# Lab_Controller_Board_v04.net
KiCad netlist of a schematic drawn in EAGLE
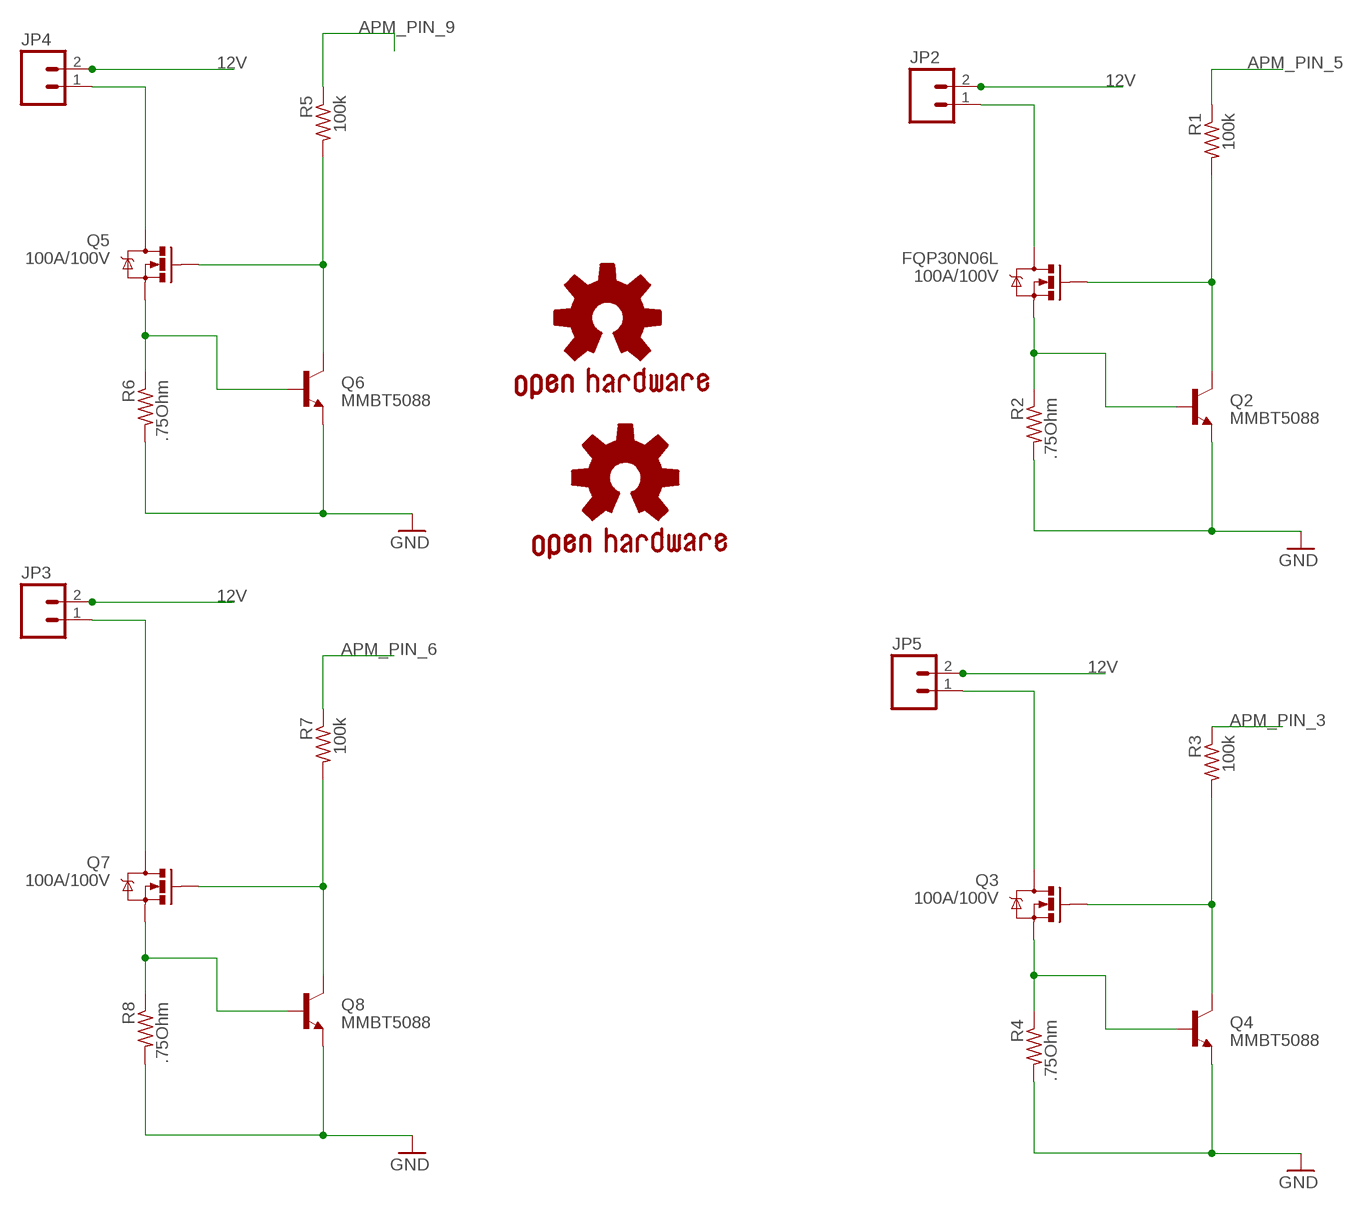
[diagram p0: schematic, sheet 1]
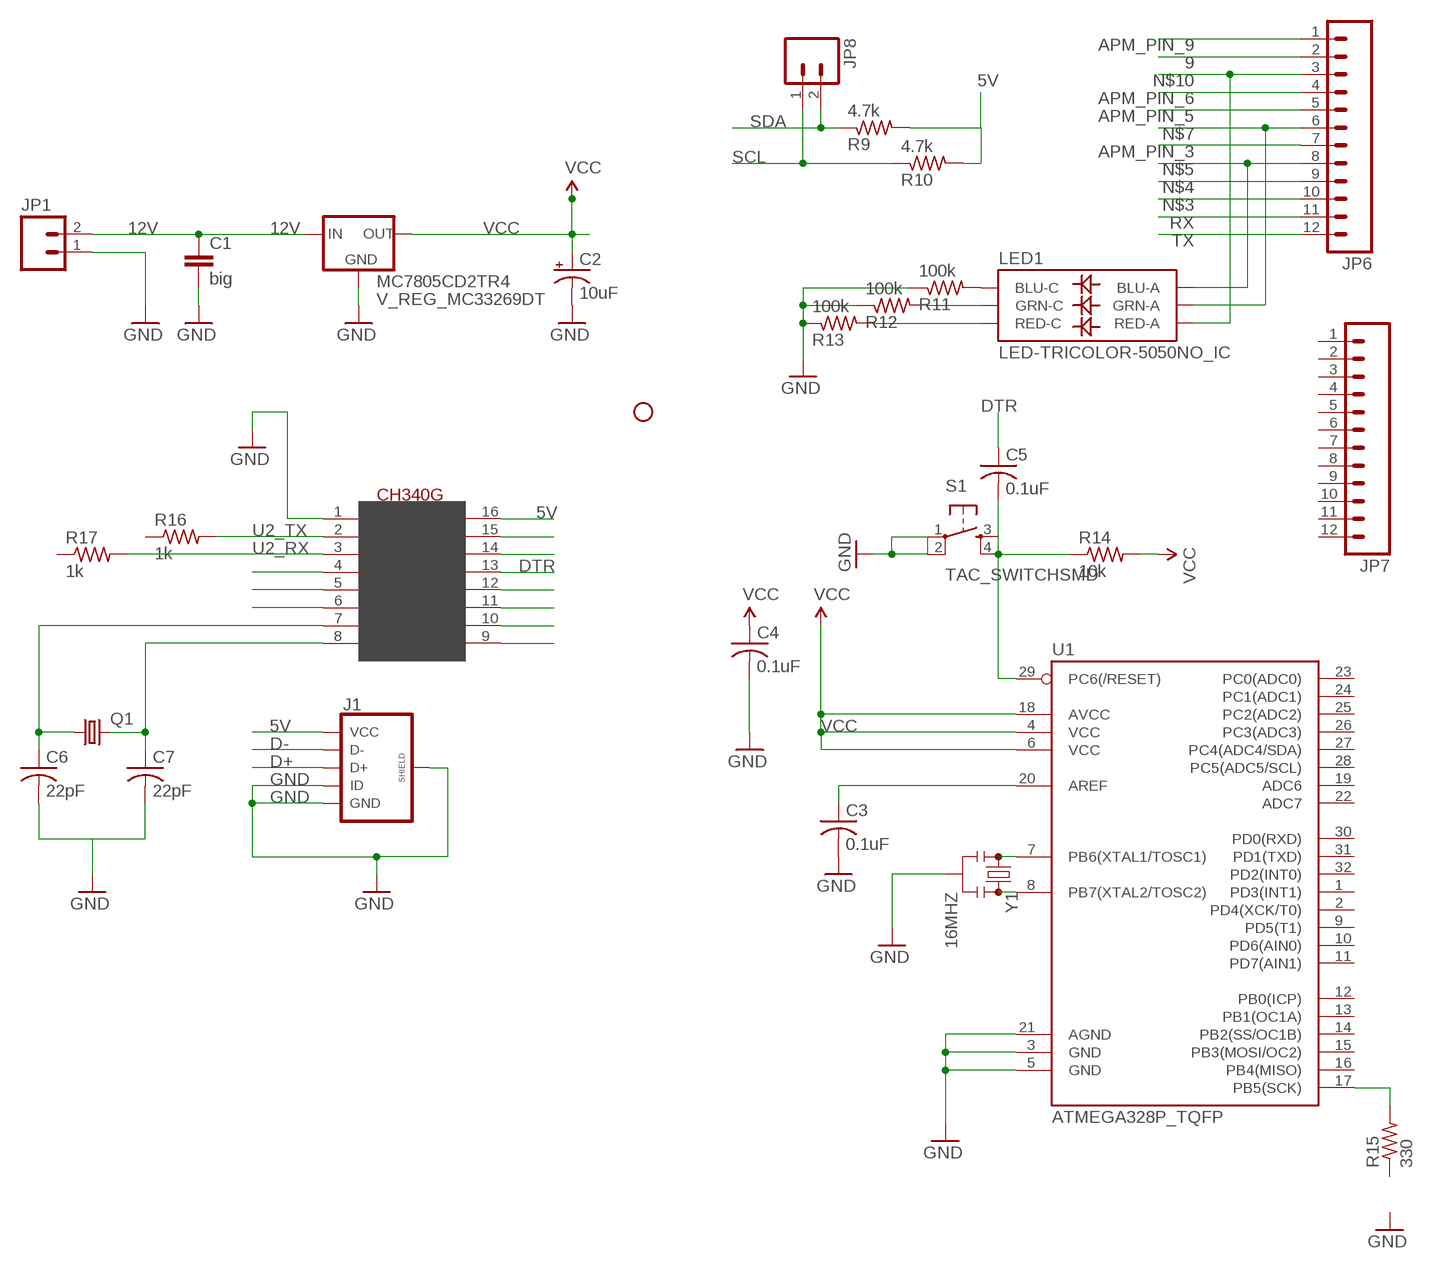
[diagram p1: schematic, sheet 2]

(export (version "E")
  (design (tool "Eeschema 10.0.6"))
  (components
    (comp (ref "FQP30N06L")
      (value "100A/100V")
      (footprint "eagle-import:TO-263_D2PAK")
      (libsource (lib "eagle-import") (part "MOSFET-NCHANNELPSMN7R0"))
    )
    (comp (ref "GOLD_ORB_SM1")
      (value "OSHWLOGO_GOLD_ORB_MED")
      (footprint "eagle-import:OSHW1")
      (libsource (lib "eagle-import") (part "OSHWLOGO_GOLD_ORB_MED"))
    )
    (comp (ref "GOLD_ORB_SM2")
      (value "OSHWLOGO_GOLD_ORB_SM")
      (footprint "eagle-import:OSHW2")
      (libsource (lib "eagle-import") (part "OSHWLOGO_GOLD_ORB_SM"))
    )
    (comp (ref "JP2")
      (value "M025MM")
      (footprint "eagle-import:SCREWTERMINAL-5MM-2")
      (libsource (lib "eagle-import") (part "M025MM"))
    )
    (comp (ref "JP3")
      (value "M025MM")
      (footprint "eagle-import:SCREWTERMINAL-5MM-2")
      (libsource (lib "eagle-import") (part "M025MM"))
    )
    (comp (ref "JP4")
      (value "M025MM")
      (footprint "eagle-import:SCREWTERMINAL-5MM-2")
      (libsource (lib "eagle-import") (part "M025MM"))
    )
    (comp (ref "JP5")
      (value "M025MM")
      (footprint "eagle-import:SCREWTERMINAL-5MM-2")
      (libsource (lib "eagle-import") (part "M025MM"))
    )
    (comp (ref "Q2")
      (value "MMBT5088")
      (footprint "eagle-import:SOT23-3")
      (libsource (lib "eagle-import") (part "TRANSISTOR_NPNMMBT5088"))
    )
    (comp (ref "Q3")
      (value "100A/100V")
      (footprint "eagle-import:TO-263_D2PAK")
      (libsource (lib "eagle-import") (part "MOSFET-NCHANNELPSMN7R0"))
    )
    (comp (ref "Q4")
      (value "MMBT5088")
      (footprint "eagle-import:SOT23-3")
      (libsource (lib "eagle-import") (part "TRANSISTOR_NPNMMBT5088"))
    )
    (comp (ref "Q5")
      (value "100A/100V")
      (footprint "eagle-import:TO-263_D2PAK")
      (libsource (lib "eagle-import") (part "MOSFET-NCHANNELPSMN7R0"))
    )
    (comp (ref "Q6")
      (value "MMBT5088")
      (footprint "eagle-import:SOT23-3")
      (libsource (lib "eagle-import") (part "TRANSISTOR_NPNMMBT5088"))
    )
    (comp (ref "Q7")
      (value "100A/100V")
      (footprint "eagle-import:TO-263_D2PAK")
      (libsource (lib "eagle-import") (part "MOSFET-NCHANNELPSMN7R0"))
    )
    (comp (ref "Q8")
      (value "MMBT5088")
      (footprint "eagle-import:SOT23-3")
      (libsource (lib "eagle-import") (part "TRANSISTOR_NPNMMBT5088"))
    )
    (comp (ref "R1")
      (value "100k")
      (footprint "eagle-import:R0805W")
      (libsource (lib "eagle-import") (part "R-US_R0805W"))
    )
    (comp (ref "R2")
      (value ".75Ohm")
      (footprint "eagle-import:0411V")
      (libsource (lib "eagle-import") (part "R-US_0411/3V"))
    )
    (comp (ref "R3")
      (value "100k")
      (footprint "eagle-import:R0805W")
      (libsource (lib "eagle-import") (part "R-US_R0805W"))
    )
    (comp (ref "R4")
      (value ".75Ohm")
      (footprint "eagle-import:0411V")
      (libsource (lib "eagle-import") (part "R-US_0411/3V"))
    )
    (comp (ref "R5")
      (value "100k")
      (footprint "eagle-import:R0805W")
      (libsource (lib "eagle-import") (part "R-US_R0805W"))
    )
    (comp (ref "R6")
      (value ".75Ohm")
      (footprint "eagle-import:0411V")
      (libsource (lib "eagle-import") (part "R-US_0411/3V"))
    )
    (comp (ref "R7")
      (value "100k")
      (footprint "eagle-import:R0805W")
      (libsource (lib "eagle-import") (part "R-US_R0805W"))
    )
    (comp (ref "R8")
      (value ".75Ohm")
      (footprint "eagle-import:0411V")
      (libsource (lib "eagle-import") (part "R-US_0411/3V"))
    )
    (comp (ref "C1")
      (value "big")
      (footprint "eagle-import:CAP-PTH-5MM")
      (libsource (lib "eagle-import") (part "CAPPTH1"))
    )
    (comp (ref "C2")
      (value "10uF")
      (footprint "eagle-import:EIA3528")
      (libsource (lib "eagle-import") (part "CAP_POL3528"))
    )
    (comp (ref "C3")
      (value "0.1uF")
      (footprint "eagle-import:C0402")
      (libsource (lib "eagle-import") (part "C-USC0402"))
    )
    (comp (ref "C4")
      (value "0.1uF")
      (footprint "eagle-import:C0402")
      (libsource (lib "eagle-import") (part "C-USC0402"))
    )
    (comp (ref "C5")
      (value "0.1uF")
      (footprint "eagle-import:C0402")
      (libsource (lib "eagle-import") (part "C-USC0402"))
    )
    (comp (ref "C6")
      (value "22pF")
      (footprint "eagle-import:C0402")
      (libsource (lib "eagle-import") (part "C-USC0402"))
    )
    (comp (ref "C7")
      (value "22pF")
      (footprint "eagle-import:C0402")
      (libsource (lib "eagle-import") (part "C-USC0402"))
    )
    (comp (ref "J1")
      (value "USB_MICROB_PLUGCONN-11752")
      (footprint "eagle-import:USB-B-MICRO-SMD_V03")
      (libsource (lib "eagle-import") (part "USB_MICROB_PLUGCONN-11752"))
    )
    (comp (ref "JP1")
      (value "M025MM")
      (footprint "eagle-import:SCREWTERMINAL-5MM-2")
      (libsource (lib "eagle-import") (part "M025MM"))
    )
    (comp (ref "JP6")
      (value "M12PTH")
      (footprint "eagle-import:1X12")
      (libsource (lib "eagle-import") (part "M12PTH"))
    )
    (comp (ref "JP7")
      (value "M12PTH")
      (footprint "eagle-import:1X12")
      (libsource (lib "eagle-import") (part "M12PTH"))
    )
    (comp (ref "JP8")
      (value "M02LOCK")
      (footprint "eagle-import:1X02_LOCK")
      (libsource (lib "eagle-import") (part "M02LOCK"))
    )
    (comp (ref "LED1")
      (value "LED-TRICOLOR-5050NO_IC")
      (footprint "eagle-import:LED-TRICOLOR-5050")
      (libsource (lib "eagle-import") (part "LED-TRICOLOR-5050NO_IC"))
    )
    (comp (ref "MC7805CD2TR4")
      (value "V_REG_MC33269DT")
      (footprint "eagle-import:DPAK")
      (libsource (lib "eagle-import") (part "V_REG_MC33269DT"))
    )
    (comp (ref "Q1")
      (value "CRYSTALHC49UP")
      (footprint "eagle-import:HC49UP")
      (libsource (lib "eagle-import") (part "CRYSTALHC49UP"))
    )
    (comp (ref "R9")
      (value "4.7k")
      (footprint "eagle-import:M0805")
      (libsource (lib "eagle-import") (part "R-US_M0805"))
    )
    (comp (ref "R10")
      (value "4.7k")
      (footprint "eagle-import:M0805")
      (libsource (lib "eagle-import") (part "R-US_M0805"))
    )
    (comp (ref "R11")
      (value "100k")
      (footprint "eagle-import:R0805W")
      (libsource (lib "eagle-import") (part "R-US_R0805W"))
    )
    (comp (ref "R12")
      (value "100k")
      (footprint "eagle-import:R0805W")
      (libsource (lib "eagle-import") (part "R-US_R0805W"))
    )
    (comp (ref "R13")
      (value "100k")
      (footprint "eagle-import:R0805W")
      (libsource (lib "eagle-import") (part "R-US_R0805W"))
    )
    (comp (ref "R14")
      (value "10k")
      (footprint "eagle-import:R0402")
      (libsource (lib "eagle-import") (part "R-US_R0402"))
    )
    (comp (ref "R15")
      (value "330")
      (footprint "eagle-import:R0402")
      (libsource (lib "eagle-import") (part "R-US_R0402"))
    )
    (comp (ref "R16")
      (value "1k")
      (footprint "eagle-import:R0402")
      (libsource (lib "eagle-import") (part "R-US_R0402"))
    )
    (comp (ref "R17")
      (value "1k")
      (footprint "eagle-import:R0402")
      (libsource (lib "eagle-import") (part "R-US_R0402"))
    )
    (comp (ref "S1")
      (value "TAC_SWITCHSMD")
      (footprint "eagle-import:TACTILE-SWITCH-SMD")
      (libsource (lib "eagle-import") (part "TAC_SWITCHSMD"))
    )
    (comp (ref "STANDOFF1")
      (value "STAND-OFF")
      (footprint "eagle-import:STAND-OFF")
      (libsource (lib "eagle-import") (part "STAND-OFF"))
    )
    (comp (ref "U1")
      (value "ATMEGA328P_TQFP")
      (footprint "eagle-import:TQFP32-08")
      (libsource (lib "eagle-import") (part "ATMEGA328P_TQFP"))
    )
    (comp (ref "U2")
      (value "CH340G")
      (footprint "eagle-import:SOIC16")
      (libsource (lib "eagle-import") (part "CH340G"))
    )
    (comp (ref "Y1")
      (value "16MHZ")
      (footprint "eagle-import:RESONATOR-SMD")
      (libsource (lib "eagle-import") (part "RESONATOR16MHZ"))
    )
  )
  (nets
    (net (code "1") (name "5V") (class "Default")
      (node (ref "J1") (pin "VBUS") (pinfunction "VCC_VBUS") (pintype "bidirectional"))
      (node (ref "R10") (pin "2") (pinfunction "2_2") (pintype "passive"))
      (node (ref "R9") (pin "2") (pinfunction "2_2") (pintype "passive"))
      (node (ref "U2") (pin "16") (pinfunction "VCC_16") (pintype "bidirectional"))
    )
    (net (code "2") (name "9") (class "Default")
      (node (ref "JP6") (pin "2") (pinfunction "2_2") (pintype "passive"))
    )
    (net (code "3") (name "12V") (class "Default")
      (node (ref "C1") (pin "1") (pinfunction "1_1") (pintype "passive"))
      (node (ref "JP1") (pin "2") (pinfunction "2_2") (pintype "passive"))
      (node (ref "JP2") (pin "2") (pinfunction "2_2") (pintype "passive"))
      (node (ref "JP3") (pin "2") (pinfunction "2_2") (pintype "passive"))
      (node (ref "JP4") (pin "2") (pinfunction "2_2") (pintype "passive"))
      (node (ref "JP5") (pin "2") (pinfunction "2_2") (pintype "passive"))
      (node (ref "MC7805CD2TR4") (pin "3") (pinfunction "IN_3") (pintype "input"))
    )
    (net (code "4") (name "APM_PIN_3") (class "Default")
      (node (ref "JP6") (pin "7") (pinfunction "7_7") (pintype "passive"))
      (node (ref "R3") (pin "1") (pinfunction "1_1") (pintype "passive"))
    )
    (net (code "5") (name "APM_PIN_5") (class "Default")
      (node (ref "JP6") (pin "5") (pinfunction "5_5") (pintype "passive"))
      (node (ref "R1") (pin "1") (pinfunction "1_1") (pintype "passive"))
    )
    (net (code "6") (name "APM_PIN_6") (class "Default")
      (node (ref "JP6") (pin "4") (pinfunction "4_4") (pintype "passive"))
      (node (ref "R7") (pin "1") (pinfunction "1_1") (pintype "passive"))
    )
    (net (code "7") (name "APM_PIN_9") (class "Default")
      (node (ref "JP6") (pin "1") (pinfunction "1_1") (pintype "passive"))
      (node (ref "R5") (pin "1") (pinfunction "1_1") (pintype "passive"))
    )
    (net (code "8") (name "D+") (class "Default")
      (node (ref "J1") (pin "D+") (pinfunction "D+_D+") (pintype "bidirectional"))
      (node (ref "U2") (pin "5") (pinfunction "D+_5") (pintype "bidirectional"))
    )
    (net (code "9") (name "D-") (class "Default")
      (node (ref "J1") (pin "D-") (pinfunction "D-_D-") (pintype "bidirectional"))
      (node (ref "U2") (pin "6") (pinfunction "D-_6") (pintype "bidirectional"))
    )
    (net (code "10") (name "DTR") (class "Default")
      (node (ref "C5") (pin "1") (pinfunction "1_1") (pintype "passive"))
      (node (ref "U2") (pin "13") (pinfunction "DTR_13") (pintype "bidirectional"))
    )
    (net (code "11") (name "GND") (class "Default")
      (node (ref "C1") (pin "2") (pinfunction "2_2") (pintype "passive"))
      (node (ref "C2") (pin "C") (pinfunction "-_C") (pintype "passive"))
      (node (ref "C3") (pin "2") (pinfunction "2_2") (pintype "passive"))
      (node (ref "C4") (pin "2") (pinfunction "2_2") (pintype "passive"))
      (node (ref "C6") (pin "2") (pinfunction "2_2") (pintype "passive"))
      (node (ref "C7") (pin "2") (pinfunction "2_2") (pintype "passive"))
      (node (ref "J1") (pin "GND") (pinfunction "GND_GND") (pintype "bidirectional"))
      (node (ref "J1") (pin "ID") (pinfunction "ID_ID") (pintype "bidirectional"))
      (node (ref "J1") (pin "SHIELD1") (pinfunction "SHIELD_SHIELD1") (pintype "bidirectional"))
      (node (ref "J1") (pin "SHIELD2") (pinfunction "SHIELD_SHIELD2") (pintype "bidirectional"))
      (node (ref "J1") (pin "SHIELD3") (pinfunction "SHIELD_SHIELD3") (pintype "bidirectional"))
      (node (ref "JP1") (pin "1") (pinfunction "1_1") (pintype "passive"))
      (node (ref "MC7805CD2TR4") (pin "1") (pinfunction "GND_1") (pintype "input"))
      (node (ref "Q2") (pin "2") (pinfunction "E_2") (pintype "passive"))
      (node (ref "Q4") (pin "2") (pinfunction "E_2") (pintype "passive"))
      (node (ref "Q6") (pin "2") (pinfunction "E_2") (pintype "passive"))
      (node (ref "Q8") (pin "2") (pinfunction "E_2") (pintype "passive"))
      (node (ref "R11") (pin "1") (pinfunction "1_1") (pintype "passive"))
      (node (ref "R12") (pin "1") (pinfunction "1_1") (pintype "passive"))
      (node (ref "R13") (pin "1") (pinfunction "1_1") (pintype "passive"))
      (node (ref "R2") (pin "2") (pinfunction "2_2") (pintype "passive"))
      (node (ref "R4") (pin "2") (pinfunction "2_2") (pintype "passive"))
      (node (ref "R6") (pin "2") (pinfunction "2_2") (pintype "passive"))
      (node (ref "R8") (pin "2") (pinfunction "2_2") (pintype "passive"))
      (node (ref "S1") (pin "1") (pinfunction "1_1") (pintype "passive"))
      (node (ref "S1") (pin "2") (pinfunction "2_2") (pintype "passive"))
      (node (ref "U1") (pin "21") (pinfunction "AGND_21") (pintype "bidirectional"))
      (node (ref "U1") (pin "3") (pinfunction "GND_3") (pintype "bidirectional"))
      (node (ref "U1") (pin "5") (pinfunction "GND_5") (pintype "bidirectional"))
      (node (ref "U2") (pin "1") (pinfunction "GND_1") (pintype "bidirectional"))
      (node (ref "Y1") (pin "2") (pinfunction "2_2") (pintype "passive"))
    )
    (net (code "12") (name "N$3") (class "Default")
      (node (ref "JP6") (pin "10") (pinfunction "10_10") (pintype "passive"))
    )
    (net (code "13") (name "N$4") (class "Default")
      (node (ref "JP6") (pin "9") (pinfunction "9_9") (pintype "passive"))
    )
    (net (code "14") (name "N$5") (class "Default")
      (node (ref "JP6") (pin "8") (pinfunction "8_8") (pintype "passive"))
      (node (ref "LED1") (pin "3") (pinfunction "BLU-A_3") (pintype "bidirectional"))
    )
    (net (code "15") (name "N$7") (class "Default")
      (node (ref "JP6") (pin "6") (pinfunction "6_6") (pintype "passive"))
      (node (ref "LED1") (pin "1") (pinfunction "GRN-A_1") (pintype "bidirectional"))
    )
    (net (code "16") (name "N$10") (class "Default")
      (node (ref "JP6") (pin "3") (pinfunction "3_3") (pintype "passive"))
      (node (ref "LED1") (pin "2") (pinfunction "RED-A_2") (pintype "bidirectional"))
    )
    (net (code "17") (name "N$30") (class "Default")
      (node (ref "U2") (pin "10") (pinfunction "DSR_10") (pintype "bidirectional"))
      (node (ref "U2") (pin "11") (pinfunction "RI_11") (pintype "bidirectional"))
      (node (ref "U2") (pin "12") (pinfunction "DCD_12") (pintype "bidirectional"))
      (node (ref "U2") (pin "14") (pinfunction "RTS_14") (pintype "bidirectional"))
      (node (ref "U2") (pin "15") (pinfunction "RS232_15") (pintype "bidirectional"))
      (node (ref "U2") (pin "9") (pinfunction "CTS_9") (pintype "bidirectional"))
    )
    (net (code "18") (name "N$32") (class "Default")
      (node (ref "C6") (pin "1") (pinfunction "1_1") (pintype "passive"))
      (node (ref "C7") (pin "1") (pinfunction "1_1") (pintype "passive"))
      (node (ref "Q1") (pin "1") (pinfunction "1_1") (pintype "passive"))
      (node (ref "Q1") (pin "2") (pinfunction "2_2") (pintype "passive"))
      (node (ref "U2") (pin "4") (pinfunction "V3_4") (pintype "bidirectional"))
      (node (ref "U2") (pin "7") (pinfunction "XI_7") (pintype "bidirectional"))
      (node (ref "U2") (pin "8") (pinfunction "XO_8") (pintype "bidirectional"))
    )
    (net (code "19") (name "Net-(FQP30N06L-D)") (class "Default")
      (node (ref "FQP30N06L") (pin "2") (pinfunction "D_2") (pintype "passive"))
      (node (ref "JP2") (pin "1") (pinfunction "1_1") (pintype "passive"))
    )
    (net (code "20") (name "Net-(FQP30N06L-G)") (class "Default")
      (node (ref "FQP30N06L") (pin "1") (pinfunction "G_1") (pintype "passive"))
      (node (ref "Q2") (pin "3") (pinfunction "C_3") (pintype "passive"))
      (node (ref "R1") (pin "2") (pinfunction "2_2") (pintype "passive"))
    )
    (net (code "21") (name "Net-(FQP30N06L-S)") (class "Default")
      (node (ref "FQP30N06L") (pin "3") (pinfunction "S_3") (pintype "passive"))
      (node (ref "Q2") (pin "1") (pinfunction "B_1") (pintype "passive"))
      (node (ref "R2") (pin "1") (pinfunction "1_1") (pintype "passive"))
    )
    (net (code "22") (name "Net-(LED1-BLU-C)") (class "Default")
      (node (ref "LED1") (pin "4") (pinfunction "BLU-C_4") (pintype "bidirectional"))
      (node (ref "R11") (pin "2") (pinfunction "2_2") (pintype "passive"))
    )
    (net (code "23") (name "Net-(LED1-GRN-C)") (class "Default")
      (node (ref "LED1") (pin "6") (pinfunction "GRN-C_6") (pintype "bidirectional"))
      (node (ref "R12") (pin "2") (pinfunction "2_2") (pintype "passive"))
    )
    (net (code "24") (name "Net-(LED1-RED-C)") (class "Default")
      (node (ref "LED1") (pin "5") (pinfunction "RED-C_5") (pintype "bidirectional"))
      (node (ref "R13") (pin "2") (pinfunction "2_2") (pintype "passive"))
    )
    (net (code "25") (name "Net-(Q3-D)") (class "Default")
      (node (ref "JP5") (pin "1") (pinfunction "1_1") (pintype "passive"))
      (node (ref "Q3") (pin "2") (pinfunction "D_2") (pintype "passive"))
    )
    (net (code "26") (name "Net-(Q3-G)") (class "Default")
      (node (ref "Q3") (pin "1") (pinfunction "G_1") (pintype "passive"))
      (node (ref "Q4") (pin "3") (pinfunction "C_3") (pintype "passive"))
      (node (ref "R3") (pin "2") (pinfunction "2_2") (pintype "passive"))
    )
    (net (code "27") (name "Net-(Q3-S)") (class "Default")
      (node (ref "Q3") (pin "3") (pinfunction "S_3") (pintype "passive"))
      (node (ref "Q4") (pin "1") (pinfunction "B_1") (pintype "passive"))
      (node (ref "R4") (pin "1") (pinfunction "1_1") (pintype "passive"))
    )
    (net (code "28") (name "Net-(Q5-D)") (class "Default")
      (node (ref "JP4") (pin "1") (pinfunction "1_1") (pintype "passive"))
      (node (ref "Q5") (pin "2") (pinfunction "D_2") (pintype "passive"))
    )
    (net (code "29") (name "Net-(Q5-G)") (class "Default")
      (node (ref "Q5") (pin "1") (pinfunction "G_1") (pintype "passive"))
      (node (ref "Q6") (pin "3") (pinfunction "C_3") (pintype "passive"))
      (node (ref "R5") (pin "2") (pinfunction "2_2") (pintype "passive"))
    )
    (net (code "30") (name "Net-(Q5-S)") (class "Default")
      (node (ref "Q5") (pin "3") (pinfunction "S_3") (pintype "passive"))
      (node (ref "Q6") (pin "1") (pinfunction "B_1") (pintype "passive"))
      (node (ref "R6") (pin "1") (pinfunction "1_1") (pintype "passive"))
    )
    (net (code "31") (name "Net-(Q7-D)") (class "Default")
      (node (ref "JP3") (pin "1") (pinfunction "1_1") (pintype "passive"))
      (node (ref "Q7") (pin "2") (pinfunction "D_2") (pintype "passive"))
    )
    (net (code "32") (name "Net-(Q7-G)") (class "Default")
      (node (ref "Q7") (pin "1") (pinfunction "G_1") (pintype "passive"))
      (node (ref "Q8") (pin "3") (pinfunction "C_3") (pintype "passive"))
      (node (ref "R7") (pin "2") (pinfunction "2_2") (pintype "passive"))
    )
    (net (code "33") (name "Net-(Q7-S)") (class "Default")
      (node (ref "Q7") (pin "3") (pinfunction "S_3") (pintype "passive"))
      (node (ref "Q8") (pin "1") (pinfunction "B_1") (pintype "passive"))
      (node (ref "R8") (pin "1") (pinfunction "1_1") (pintype "passive"))
    )
    (net (code "34") (name "Net-(U1-AREF)") (class "Default")
      (node (ref "C3") (pin "1") (pinfunction "1_1") (pintype "passive"))
      (node (ref "U1") (pin "20") (pinfunction "AREF_20") (pintype "bidirectional"))
    )
    (net (code "35") (name "Net-(U1-PB5(SCK))") (class "Default")
      (node (ref "R15") (pin "2") (pinfunction "2_2") (pintype "passive"))
      (node (ref "U1") (pin "17") (pinfunction "PB5(SCK)_17") (pintype "bidirectional"))
    )
    (net (code "36") (name "Net-(U1-PB6(XTAL1{slash}TOSC1))") (class "Default")
      (node (ref "U1") (pin "7") (pinfunction "PB6(XTAL1/TOSC1)_7") (pintype "bidirectional"))
      (node (ref "Y1") (pin "1") (pinfunction "1_1") (pintype "passive"))
    )
    (net (code "37") (name "Net-(U1-PB7(XTAL2{slash}TOSC2))") (class "Default")
      (node (ref "U1") (pin "8") (pinfunction "PB7(XTAL2/TOSC2)_8") (pintype "bidirectional"))
      (node (ref "Y1") (pin "3") (pinfunction "3_3") (pintype "passive"))
    )
    (net (code "38") (name "Net-(U1-PC6({slash}RESET))") (class "Default")
      (node (ref "C5") (pin "2") (pinfunction "2_2") (pintype "passive"))
      (node (ref "R14") (pin "1") (pinfunction "1_1") (pintype "passive"))
      (node (ref "S1") (pin "3") (pinfunction "3_3") (pintype "passive"))
      (node (ref "S1") (pin "4") (pinfunction "4_4") (pintype "passive"))
      (node (ref "U1") (pin "29") (pinfunction "PC6(/RESET)_29") (pintype "bidirectional"))
    )
    (net (code "39") (name "RX") (class "Default")
      (node (ref "JP6") (pin "11") (pinfunction "11_11") (pintype "passive"))
    )
    (net (code "40") (name "SCL") (class "Default")
      (node (ref "JP8") (pin "1") (pinfunction "1_1") (pintype "passive"))
      (node (ref "R10") (pin "1") (pinfunction "1_1") (pintype "passive"))
    )
    (net (code "41") (name "SDA") (class "Default")
      (node (ref "JP8") (pin "2") (pinfunction "2_2") (pintype "passive"))
      (node (ref "R9") (pin "1") (pinfunction "1_1") (pintype "passive"))
    )
    (net (code "42") (name "TX") (class "Default")
      (node (ref "JP6") (pin "12") (pinfunction "12_12") (pintype "passive"))
    )
    (net (code "43") (name "U2_RX") (class "Default")
      (node (ref "R17") (pin "2") (pinfunction "2_2") (pintype "passive"))
      (node (ref "U2") (pin "3") (pinfunction "RX_3") (pintype "bidirectional"))
    )
    (net (code "44") (name "U2_TX") (class "Default")
      (node (ref "R16") (pin "2") (pinfunction "2_2") (pintype "passive"))
      (node (ref "U2") (pin "2") (pinfunction "TX_2") (pintype "bidirectional"))
    )
    (net (code "45") (name "VCC") (class "Default")
      (node (ref "C2") (pin "A") (pinfunction "+_A") (pintype "passive"))
      (node (ref "C4") (pin "1") (pinfunction "1_1") (pintype "passive"))
      (node (ref "MC7805CD2TR4") (pin "4") (pinfunction "OUT_4") (pintype "passive"))
      (node (ref "R14") (pin "2") (pinfunction "2_2") (pintype "passive"))
      (node (ref "U1") (pin "18") (pinfunction "AVCC_18") (pintype "bidirectional"))
      (node (ref "U1") (pin "4") (pinfunction "VCC_4") (pintype "bidirectional"))
      (node (ref "U1") (pin "6") (pinfunction "VCC_6") (pintype "bidirectional"))
    )
    (net (code "46") (name "unconnected-(JP7-Pad1)") (class "Default")
      (node (ref "JP7") (pin "1") (pinfunction "1_1") (pintype "passive"))
    )
    (net (code "47") (name "unconnected-(JP7-Pad2)") (class "Default")
      (node (ref "JP7") (pin "2") (pinfunction "2_2") (pintype "passive"))
    )
    (net (code "48") (name "unconnected-(JP7-Pad3)") (class "Default")
      (node (ref "JP7") (pin "3") (pinfunction "3_3") (pintype "passive"))
    )
    (net (code "49") (name "unconnected-(JP7-Pad4)") (class "Default")
      (node (ref "JP7") (pin "4") (pinfunction "4_4") (pintype "passive"))
    )
    (net (code "50") (name "unconnected-(JP7-Pad5)") (class "Default")
      (node (ref "JP7") (pin "5") (pinfunction "5_5") (pintype "passive"))
    )
    (net (code "51") (name "unconnected-(JP7-Pad6)") (class "Default")
      (node (ref "JP7") (pin "6") (pinfunction "6_6") (pintype "passive"))
    )
    (net (code "52") (name "unconnected-(JP7-Pad7)") (class "Default")
      (node (ref "JP7") (pin "7") (pinfunction "7_7") (pintype "passive"))
    )
    (net (code "53") (name "unconnected-(JP7-Pad8)") (class "Default")
      (node (ref "JP7") (pin "8") (pinfunction "8_8") (pintype "passive"))
    )
    (net (code "54") (name "unconnected-(JP7-Pad9)") (class "Default")
      (node (ref "JP7") (pin "9") (pinfunction "9_9") (pintype "passive"))
    )
    (net (code "55") (name "unconnected-(JP7-Pad10)") (class "Default")
      (node (ref "JP7") (pin "10") (pinfunction "10_10") (pintype "passive"))
    )
    (net (code "56") (name "unconnected-(JP7-Pad11)") (class "Default")
      (node (ref "JP7") (pin "11") (pinfunction "11_11") (pintype "passive"))
    )
    (net (code "57") (name "unconnected-(JP7-Pad12)") (class "Default")
      (node (ref "JP7") (pin "12") (pinfunction "12_12") (pintype "passive"))
    )
    (net (code "58") (name "unconnected-(R15-Pad1)") (class "Default")
      (node (ref "R15") (pin "1") (pinfunction "1_1") (pintype "passive"))
    )
    (net (code "59") (name "unconnected-(R16-Pad1)") (class "Default")
      (node (ref "R16") (pin "1") (pinfunction "1_1") (pintype "passive"))
    )
    (net (code "60") (name "unconnected-(R17-Pad1)") (class "Default")
      (node (ref "R17") (pin "1") (pinfunction "1_1") (pintype "passive"))
    )
    (net (code "61") (name "unconnected-(U1-ADC6-Pad19)") (class "Default")
      (node (ref "U1") (pin "19") (pinfunction "ADC6_19") (pintype "bidirectional"))
    )
    (net (code "62") (name "unconnected-(U1-ADC7-Pad22)") (class "Default")
      (node (ref "U1") (pin "22") (pinfunction "ADC7_22") (pintype "bidirectional"))
    )
    (net (code "63") (name "unconnected-(U1-PB0(ICP)-Pad12)") (class "Default")
      (node (ref "U1") (pin "12") (pinfunction "PB0(ICP)_12") (pintype "bidirectional"))
    )
    (net (code "64") (name "unconnected-(U1-PB1(OC1A)-Pad13)") (class "Default")
      (node (ref "U1") (pin "13") (pinfunction "PB1(OC1A)_13") (pintype "bidirectional"))
    )
    (net (code "65") (name "unconnected-(U1-PB2(SS{slash}OC1B)-Pad14)") (class "Default")
      (node (ref "U1") (pin "14") (pinfunction "PB2(SS/OC1B)_14") (pintype "bidirectional"))
    )
    (net (code "66") (name "unconnected-(U1-PB3(MOSI{slash}OC2)-Pad15)") (class "Default")
      (node (ref "U1") (pin "15") (pinfunction "PB3(MOSI/OC2)_15") (pintype "bidirectional"))
    )
    (net (code "67") (name "unconnected-(U1-PB4(MISO)-Pad16)") (class "Default")
      (node (ref "U1") (pin "16") (pinfunction "PB4(MISO)_16") (pintype "bidirectional"))
    )
    (net (code "68") (name "unconnected-(U1-PC0(ADC0)-Pad23)") (class "Default")
      (node (ref "U1") (pin "23") (pinfunction "PC0(ADC0)_23") (pintype "bidirectional"))
    )
    (net (code "69") (name "unconnected-(U1-PC1(ADC1)-Pad24)") (class "Default")
      (node (ref "U1") (pin "24") (pinfunction "PC1(ADC1)_24") (pintype "bidirectional"))
    )
    (net (code "70") (name "unconnected-(U1-PC2(ADC2)-Pad25)") (class "Default")
      (node (ref "U1") (pin "25") (pinfunction "PC2(ADC2)_25") (pintype "bidirectional"))
    )
    (net (code "71") (name "unconnected-(U1-PC3(ADC3)-Pad26)") (class "Default")
      (node (ref "U1") (pin "26") (pinfunction "PC3(ADC3)_26") (pintype "bidirectional"))
    )
    (net (code "72") (name "unconnected-(U1-PC4(ADC4{slash}SDA)-Pad27)") (class "Default")
      (node (ref "U1") (pin "27") (pinfunction "PC4(ADC4/SDA)_27") (pintype "bidirectional"))
    )
    (net (code "73") (name "unconnected-(U1-PC5(ADC5{slash}SCL)-Pad28)") (class "Default")
      (node (ref "U1") (pin "28") (pinfunction "PC5(ADC5/SCL)_28") (pintype "bidirectional"))
    )
    (net (code "74") (name "unconnected-(U1-PD0(RXD)-Pad30)") (class "Default")
      (node (ref "U1") (pin "30") (pinfunction "PD0(RXD)_30") (pintype "bidirectional"))
    )
    (net (code "75") (name "unconnected-(U1-PD1(TXD)-Pad31)") (class "Default")
      (node (ref "U1") (pin "31") (pinfunction "PD1(TXD)_31") (pintype "bidirectional"))
    )
    (net (code "76") (name "unconnected-(U1-PD2(INT0)-Pad32)") (class "Default")
      (node (ref "U1") (pin "32") (pinfunction "PD2(INT0)_32") (pintype "bidirectional"))
    )
    (net (code "77") (name "unconnected-(U1-PD3(INT1)-Pad1)") (class "Default")
      (node (ref "U1") (pin "1") (pinfunction "PD3(INT1)_1") (pintype "bidirectional"))
    )
    (net (code "78") (name "unconnected-(U1-PD4(XCK{slash}T0)-Pad2)") (class "Default")
      (node (ref "U1") (pin "2") (pinfunction "PD4(XCK/T0)_2") (pintype "bidirectional"))
    )
    (net (code "79") (name "unconnected-(U1-PD5(T1)-Pad9)") (class "Default")
      (node (ref "U1") (pin "9") (pinfunction "PD5(T1)_9") (pintype "bidirectional"))
    )
    (net (code "80") (name "unconnected-(U1-PD6(AIN0)-Pad10)") (class "Default")
      (node (ref "U1") (pin "10") (pinfunction "PD6(AIN0)_10") (pintype "bidirectional"))
    )
    (net (code "81") (name "unconnected-(U1-PD7(AIN1)-Pad11)") (class "Default")
      (node (ref "U1") (pin "11") (pinfunction "PD7(AIN1)_11") (pintype "bidirectional"))
    )
  )
)
